# S107D.net
KiCad netlist of a schematic drawn in EAGLE
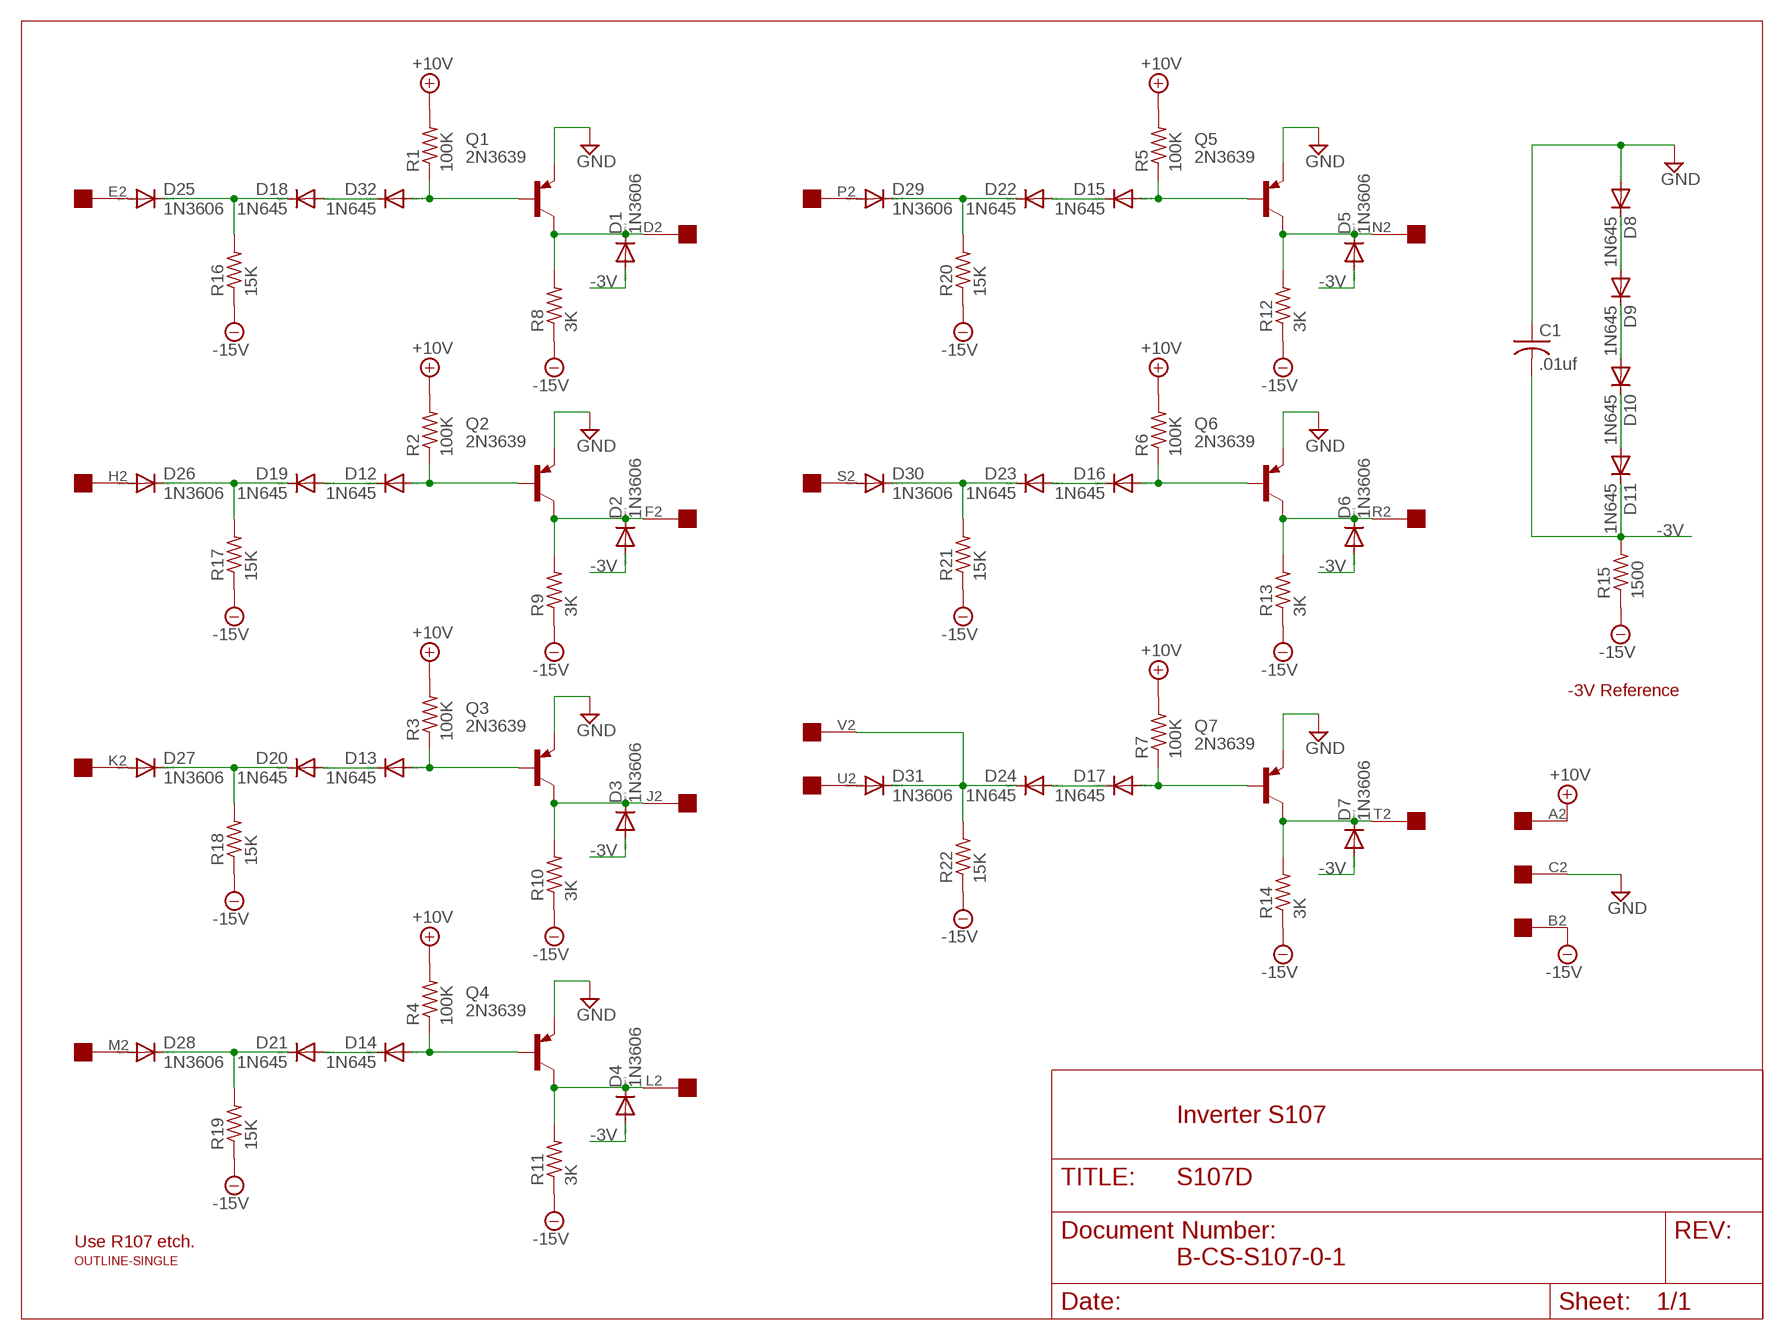
[diagram p0: schematic, sheet 1]

(export (version "E")
  (design (tool "Eeschema 10.0.6"))
  (components
    (comp (ref "C1")
      (value ".01uf")
      (footprint "eagle-import:C050-025X075")
      (libsource (lib "eagle-import") (part "C-US050-025X075"))
    )
    (comp (ref "D1")
      (value "1N3606")
      (footprint "eagle-import:DO35-10")
      (libsource (lib "eagle-import") (part "1N4148DO35-10"))
    )
    (comp (ref "D2")
      (value "1N3606")
      (footprint "eagle-import:DO35-10")
      (libsource (lib "eagle-import") (part "1N4148DO35-10"))
    )
    (comp (ref "D3")
      (value "1N3606")
      (footprint "eagle-import:DO35-10")
      (libsource (lib "eagle-import") (part "1N4148DO35-10"))
    )
    (comp (ref "D4")
      (value "1N3606")
      (footprint "eagle-import:DO35-10")
      (libsource (lib "eagle-import") (part "1N4148DO35-10"))
    )
    (comp (ref "D5")
      (value "1N3606")
      (footprint "eagle-import:DO35-10")
      (libsource (lib "eagle-import") (part "1N4148DO35-10"))
    )
    (comp (ref "D6")
      (value "1N3606")
      (footprint "eagle-import:DO35-10")
      (libsource (lib "eagle-import") (part "1N4148DO35-10"))
    )
    (comp (ref "D7")
      (value "1N3606")
      (footprint "eagle-import:DO35-10")
      (libsource (lib "eagle-import") (part "1N4148DO35-10"))
    )
    (comp (ref "D8")
      (value "1N645")
      (footprint "eagle-import:DO35-10")
      (libsource (lib "eagle-import") (part "1N4148DO35-10"))
    )
    (comp (ref "D9")
      (value "1N645")
      (footprint "eagle-import:DO35-10")
      (libsource (lib "eagle-import") (part "1N4148DO35-10"))
    )
    (comp (ref "D10")
      (value "1N645")
      (footprint "eagle-import:DO35-10")
      (libsource (lib "eagle-import") (part "1N4148DO35-10"))
    )
    (comp (ref "D11")
      (value "1N645")
      (footprint "eagle-import:DO35-10")
      (libsource (lib "eagle-import") (part "1N4148DO35-10"))
    )
    (comp (ref "D12")
      (value "1N645")
      (footprint "eagle-import:DO35-10")
      (libsource (lib "eagle-import") (part "1N4148DO35-10"))
    )
    (comp (ref "D13")
      (value "1N645")
      (footprint "eagle-import:DO35-10")
      (libsource (lib "eagle-import") (part "1N4148DO35-10"))
    )
    (comp (ref "D14")
      (value "1N645")
      (footprint "eagle-import:DO35-10")
      (libsource (lib "eagle-import") (part "1N4148DO35-10"))
    )
    (comp (ref "D15")
      (value "1N645")
      (footprint "eagle-import:DO35-10")
      (libsource (lib "eagle-import") (part "1N4148DO35-10"))
    )
    (comp (ref "D16")
      (value "1N645")
      (footprint "eagle-import:DO35-10")
      (libsource (lib "eagle-import") (part "1N4148DO35-10"))
    )
    (comp (ref "D17")
      (value "1N645")
      (footprint "eagle-import:DO35-10")
      (libsource (lib "eagle-import") (part "1N4148DO35-10"))
    )
    (comp (ref "D18")
      (value "1N645")
      (footprint "eagle-import:DO35-10")
      (libsource (lib "eagle-import") (part "1N4148DO35-10"))
    )
    (comp (ref "D19")
      (value "1N645")
      (footprint "eagle-import:DO35-10")
      (libsource (lib "eagle-import") (part "1N4148DO35-10"))
    )
    (comp (ref "D20")
      (value "1N645")
      (footprint "eagle-import:DO35-10")
      (libsource (lib "eagle-import") (part "1N4148DO35-10"))
    )
    (comp (ref "D21")
      (value "1N645")
      (footprint "eagle-import:DO35-10")
      (libsource (lib "eagle-import") (part "1N4148DO35-10"))
    )
    (comp (ref "D22")
      (value "1N645")
      (footprint "eagle-import:DO35-10")
      (libsource (lib "eagle-import") (part "1N4148DO35-10"))
    )
    (comp (ref "D23")
      (value "1N645")
      (footprint "eagle-import:DO35-10")
      (libsource (lib "eagle-import") (part "1N4148DO35-10"))
    )
    (comp (ref "D24")
      (value "1N645")
      (footprint "eagle-import:DO35-10")
      (libsource (lib "eagle-import") (part "1N4148DO35-10"))
    )
    (comp (ref "D25")
      (value "1N3606")
      (footprint "eagle-import:DO35-10")
      (libsource (lib "eagle-import") (part "1N4148DO35-10"))
    )
    (comp (ref "D26")
      (value "1N3606")
      (footprint "eagle-import:DO35-10")
      (libsource (lib "eagle-import") (part "1N4148DO35-10"))
    )
    (comp (ref "D27")
      (value "1N3606")
      (footprint "eagle-import:DO35-10")
      (libsource (lib "eagle-import") (part "1N4148DO35-10"))
    )
    (comp (ref "D28")
      (value "1N3606")
      (footprint "eagle-import:DO35-10")
      (libsource (lib "eagle-import") (part "1N4148DO35-10"))
    )
    (comp (ref "D29")
      (value "1N3606")
      (footprint "eagle-import:DO35-10")
      (libsource (lib "eagle-import") (part "1N4148DO35-10"))
    )
    (comp (ref "D30")
      (value "1N3606")
      (footprint "eagle-import:DO35-10")
      (libsource (lib "eagle-import") (part "1N4148DO35-10"))
    )
    (comp (ref "D31")
      (value "1N3606")
      (footprint "eagle-import:DO35-10")
      (libsource (lib "eagle-import") (part "1N4148DO35-10"))
    )
    (comp (ref "D32")
      (value "1N645")
      (footprint "eagle-import:DO35-10")
      (libsource (lib "eagle-import") (part "1N4148DO35-10"))
    )
    (comp (ref "Q1")
      (value "2N3639")
      (footprint "eagle-import:TO39")
      (libsource (lib "eagle-import") (part "2N3637"))
    )
    (comp (ref "Q2")
      (value "2N3639")
      (footprint "eagle-import:TO39")
      (libsource (lib "eagle-import") (part "2N3637"))
    )
    (comp (ref "Q3")
      (value "2N3639")
      (footprint "eagle-import:TO39")
      (libsource (lib "eagle-import") (part "2N3637"))
    )
    (comp (ref "Q4")
      (value "2N3639")
      (footprint "eagle-import:TO39")
      (libsource (lib "eagle-import") (part "2N3637"))
    )
    (comp (ref "Q5")
      (value "2N3639")
      (footprint "eagle-import:TO39")
      (libsource (lib "eagle-import") (part "2N3637"))
    )
    (comp (ref "Q6")
      (value "2N3639")
      (footprint "eagle-import:TO39")
      (libsource (lib "eagle-import") (part "2N3637"))
    )
    (comp (ref "Q7")
      (value "2N3639")
      (footprint "eagle-import:TO39")
      (libsource (lib "eagle-import") (part "2N3637"))
    )
    (comp (ref "R1")
      (value "100K")
      (footprint "eagle-import:0207_10")
      (libsource (lib "eagle-import") (part "R-US_0207/10"))
    )
    (comp (ref "R2")
      (value "100K")
      (footprint "eagle-import:0207_10")
      (libsource (lib "eagle-import") (part "R-US_0207/10"))
    )
    (comp (ref "R3")
      (value "100K")
      (footprint "eagle-import:0207_10")
      (libsource (lib "eagle-import") (part "R-US_0207/10"))
    )
    (comp (ref "R4")
      (value "100K")
      (footprint "eagle-import:0207_10")
      (libsource (lib "eagle-import") (part "R-US_0207/10"))
    )
    (comp (ref "R5")
      (value "100K")
      (footprint "eagle-import:0207_10")
      (libsource (lib "eagle-import") (part "R-US_0207/10"))
    )
    (comp (ref "R6")
      (value "100K")
      (footprint "eagle-import:0207_10")
      (libsource (lib "eagle-import") (part "R-US_0207/10"))
    )
    (comp (ref "R7")
      (value "100K")
      (footprint "eagle-import:0207_10")
      (libsource (lib "eagle-import") (part "R-US_0207/10"))
    )
    (comp (ref "R8")
      (value "3K")
      (footprint "eagle-import:0207_10")
      (libsource (lib "eagle-import") (part "R-US_0207/10"))
    )
    (comp (ref "R9")
      (value "3K")
      (footprint "eagle-import:0207_10")
      (libsource (lib "eagle-import") (part "R-US_0207/10"))
    )
    (comp (ref "R10")
      (value "3K")
      (footprint "eagle-import:0207_10")
      (libsource (lib "eagle-import") (part "R-US_0207/10"))
    )
    (comp (ref "R11")
      (value "3K")
      (footprint "eagle-import:0207_10")
      (libsource (lib "eagle-import") (part "R-US_0207/10"))
    )
    (comp (ref "R12")
      (value "3K")
      (footprint "eagle-import:0207_10")
      (libsource (lib "eagle-import") (part "R-US_0207/10"))
    )
    (comp (ref "R13")
      (value "3K")
      (footprint "eagle-import:0207_10")
      (libsource (lib "eagle-import") (part "R-US_0207/10"))
    )
    (comp (ref "R14")
      (value "3K")
      (footprint "eagle-import:0207_10")
      (libsource (lib "eagle-import") (part "R-US_0207/10"))
    )
    (comp (ref "R15")
      (value "1500")
      (footprint "eagle-import:0207_10")
      (libsource (lib "eagle-import") (part "R-US_0207/10"))
    )
    (comp (ref "R16")
      (value "15K")
      (footprint "eagle-import:0207_10")
      (libsource (lib "eagle-import") (part "R-US_0207/10"))
    )
    (comp (ref "R17")
      (value "15K")
      (footprint "eagle-import:0207_10")
      (libsource (lib "eagle-import") (part "R-US_0207/10"))
    )
    (comp (ref "R18")
      (value "15K")
      (footprint "eagle-import:0207_10")
      (libsource (lib "eagle-import") (part "R-US_0207/10"))
    )
    (comp (ref "R19")
      (value "15K")
      (footprint "eagle-import:0207_10")
      (libsource (lib "eagle-import") (part "R-US_0207/10"))
    )
    (comp (ref "R20")
      (value "15K")
      (footprint "eagle-import:0207_10")
      (libsource (lib "eagle-import") (part "R-US_0207/10"))
    )
    (comp (ref "R21")
      (value "15K")
      (footprint "eagle-import:0207_10")
      (libsource (lib "eagle-import") (part "R-US_0207/10"))
    )
    (comp (ref "R22")
      (value "15K")
      (footprint "eagle-import:0207_10")
      (libsource (lib "eagle-import") (part "R-US_0207/10"))
    )
    (comp (ref "U$1")
      (value "OUTLINE-SINGLE")
      (footprint "eagle-import:SINGLE")
      (libsource (lib "eagle-import") (part "OUTLINE-SINGLE"))
    )
    (comp (ref "U$2")
      (value "EDGE-1")
      (footprint "eagle-import:EDGE-CON1")
      (libsource (lib "eagle-import") (part "EDGE-1"))
    )
  )
  (nets
    (net (code "1") (name "+10V") (class "Default")
      (node (ref "R1") (pin "2") (pinfunction "2_2") (pintype "passive"))
      (node (ref "R2") (pin "2") (pinfunction "2_2") (pintype "passive"))
      (node (ref "R3") (pin "2") (pinfunction "2_2") (pintype "passive"))
      (node (ref "R4") (pin "2") (pinfunction "2_2") (pintype "passive"))
      (node (ref "R5") (pin "2") (pinfunction "2_2") (pintype "passive"))
      (node (ref "R6") (pin "2") (pinfunction "2_2") (pintype "passive"))
      (node (ref "R7") (pin "2") (pinfunction "2_2") (pintype "passive"))
      (node (ref "U$2") (pin "A2") (pinfunction "1_A2") (pintype "bidirectional"))
    )
    (net (code "2") (name "-15V") (class "Default")
      (node (ref "R10") (pin "1") (pinfunction "1_1") (pintype "passive"))
      (node (ref "R11") (pin "1") (pinfunction "1_1") (pintype "passive"))
      (node (ref "R12") (pin "1") (pinfunction "1_1") (pintype "passive"))
      (node (ref "R13") (pin "1") (pinfunction "1_1") (pintype "passive"))
      (node (ref "R14") (pin "1") (pinfunction "1_1") (pintype "passive"))
      (node (ref "R15") (pin "1") (pinfunction "1_1") (pintype "passive"))
      (node (ref "R16") (pin "1") (pinfunction "1_1") (pintype "passive"))
      (node (ref "R17") (pin "1") (pinfunction "1_1") (pintype "passive"))
      (node (ref "R18") (pin "1") (pinfunction "1_1") (pintype "passive"))
      (node (ref "R19") (pin "1") (pinfunction "1_1") (pintype "passive"))
      (node (ref "R20") (pin "1") (pinfunction "1_1") (pintype "passive"))
      (node (ref "R21") (pin "1") (pinfunction "1_1") (pintype "passive"))
      (node (ref "R22") (pin "1") (pinfunction "1_1") (pintype "passive"))
      (node (ref "R8") (pin "1") (pinfunction "1_1") (pintype "passive"))
      (node (ref "R9") (pin "1") (pinfunction "1_1") (pintype "passive"))
      (node (ref "U$2") (pin "B2") (pinfunction "1_B2") (pintype "bidirectional"))
    )
    (net (code "3") (name "/-3V") (class "Default")
      (node (ref "C1") (pin "2") (pinfunction "2_2") (pintype "passive"))
      (node (ref "D1") (pin "A") (pinfunction "A_A") (pintype "passive"))
      (node (ref "D11") (pin "C") (pinfunction "C_C") (pintype "passive"))
      (node (ref "D2") (pin "A") (pinfunction "A_A") (pintype "passive"))
      (node (ref "D3") (pin "A") (pinfunction "A_A") (pintype "passive"))
      (node (ref "D4") (pin "A") (pinfunction "A_A") (pintype "passive"))
      (node (ref "D5") (pin "A") (pinfunction "A_A") (pintype "passive"))
      (node (ref "D6") (pin "A") (pinfunction "A_A") (pintype "passive"))
      (node (ref "D7") (pin "A") (pinfunction "A_A") (pintype "passive"))
      (node (ref "R15") (pin "2") (pinfunction "2_2") (pintype "passive"))
    )
    (net (code "4") (name "GND") (class "Default")
      (node (ref "C1") (pin "1") (pinfunction "1_1") (pintype "passive"))
      (node (ref "D8") (pin "A") (pinfunction "A_A") (pintype "passive"))
      (node (ref "Q1") (pin "1") (pinfunction "E_1") (pintype "passive"))
      (node (ref "Q2") (pin "1") (pinfunction "E_1") (pintype "passive"))
      (node (ref "Q3") (pin "1") (pinfunction "E_1") (pintype "passive"))
      (node (ref "Q4") (pin "1") (pinfunction "E_1") (pintype "passive"))
      (node (ref "Q5") (pin "1") (pinfunction "E_1") (pintype "passive"))
      (node (ref "Q6") (pin "1") (pinfunction "E_1") (pintype "passive"))
      (node (ref "Q7") (pin "1") (pinfunction "E_1") (pintype "passive"))
      (node (ref "U$2") (pin "C2") (pinfunction "1_C2") (pintype "bidirectional"))
    )
    (net (code "5") (name "Net-(D8-PadC)") (class "Default")
      (node (ref "D8") (pin "C") (pinfunction "C_C") (pintype "passive"))
      (node (ref "D9") (pin "A") (pinfunction "A_A") (pintype "passive"))
    )
    (net (code "6") (name "Net-(D10-PadA)") (class "Default")
      (node (ref "D10") (pin "A") (pinfunction "A_A") (pintype "passive"))
      (node (ref "D9") (pin "C") (pinfunction "C_C") (pintype "passive"))
    )
    (net (code "7") (name "Net-(D10-PadC)") (class "Default")
      (node (ref "D10") (pin "C") (pinfunction "C_C") (pintype "passive"))
      (node (ref "D11") (pin "A") (pinfunction "A_A") (pintype "passive"))
    )
    (net (code "8") (name "Net-(D12-PadC)") (class "Default")
      (node (ref "D12") (pin "C") (pinfunction "C_C") (pintype "passive"))
      (node (ref "D19") (pin "A") (pinfunction "A_A") (pintype "passive"))
    )
    (net (code "9") (name "Net-(D13-PadC)") (class "Default")
      (node (ref "D13") (pin "C") (pinfunction "C_C") (pintype "passive"))
      (node (ref "D20") (pin "A") (pinfunction "A_A") (pintype "passive"))
    )
    (net (code "10") (name "Net-(D14-PadC)") (class "Default")
      (node (ref "D14") (pin "C") (pinfunction "C_C") (pintype "passive"))
      (node (ref "D21") (pin "A") (pinfunction "A_A") (pintype "passive"))
    )
    (net (code "11") (name "Net-(D15-PadC)") (class "Default")
      (node (ref "D15") (pin "C") (pinfunction "C_C") (pintype "passive"))
      (node (ref "D22") (pin "A") (pinfunction "A_A") (pintype "passive"))
    )
    (net (code "12") (name "Net-(D16-PadC)") (class "Default")
      (node (ref "D16") (pin "C") (pinfunction "C_C") (pintype "passive"))
      (node (ref "D23") (pin "A") (pinfunction "A_A") (pintype "passive"))
    )
    (net (code "13") (name "Net-(D17-PadC)") (class "Default")
      (node (ref "D17") (pin "C") (pinfunction "C_C") (pintype "passive"))
      (node (ref "D24") (pin "A") (pinfunction "A_A") (pintype "passive"))
    )
    (net (code "14") (name "Net-(D18-PadA)") (class "Default")
      (node (ref "D18") (pin "A") (pinfunction "A_A") (pintype "passive"))
      (node (ref "D32") (pin "C") (pinfunction "C_C") (pintype "passive"))
    )
    (net (code "15") (name "Net-(D18-PadC)") (class "Default")
      (node (ref "D18") (pin "C") (pinfunction "C_C") (pintype "passive"))
      (node (ref "D25") (pin "C") (pinfunction "C_C") (pintype "passive"))
      (node (ref "R16") (pin "2") (pinfunction "2_2") (pintype "passive"))
    )
    (net (code "16") (name "Net-(D19-PadC)") (class "Default")
      (node (ref "D19") (pin "C") (pinfunction "C_C") (pintype "passive"))
      (node (ref "D26") (pin "C") (pinfunction "C_C") (pintype "passive"))
      (node (ref "R17") (pin "2") (pinfunction "2_2") (pintype "passive"))
    )
    (net (code "17") (name "Net-(D20-PadC)") (class "Default")
      (node (ref "D20") (pin "C") (pinfunction "C_C") (pintype "passive"))
      (node (ref "D27") (pin "C") (pinfunction "C_C") (pintype "passive"))
      (node (ref "R18") (pin "2") (pinfunction "2_2") (pintype "passive"))
    )
    (net (code "18") (name "Net-(D21-PadC)") (class "Default")
      (node (ref "D21") (pin "C") (pinfunction "C_C") (pintype "passive"))
      (node (ref "D28") (pin "C") (pinfunction "C_C") (pintype "passive"))
      (node (ref "R19") (pin "2") (pinfunction "2_2") (pintype "passive"))
    )
    (net (code "19") (name "Net-(D22-PadC)") (class "Default")
      (node (ref "D22") (pin "C") (pinfunction "C_C") (pintype "passive"))
      (node (ref "D29") (pin "C") (pinfunction "C_C") (pintype "passive"))
      (node (ref "R20") (pin "2") (pinfunction "2_2") (pintype "passive"))
    )
    (net (code "20") (name "Net-(D23-PadC)") (class "Default")
      (node (ref "D23") (pin "C") (pinfunction "C_C") (pintype "passive"))
      (node (ref "D30") (pin "C") (pinfunction "C_C") (pintype "passive"))
      (node (ref "R21") (pin "2") (pinfunction "2_2") (pintype "passive"))
    )
    (net (code "21") (name "Net-(Q1-B)") (class "Default")
      (node (ref "D32") (pin "A") (pinfunction "A_A") (pintype "passive"))
      (node (ref "Q1") (pin "2") (pinfunction "B_2") (pintype "passive"))
      (node (ref "R1") (pin "1") (pinfunction "1_1") (pintype "passive"))
    )
    (net (code "22") (name "Net-(Q1-C)") (class "Default")
      (node (ref "D1") (pin "C") (pinfunction "C_C") (pintype "passive"))
      (node (ref "Q1") (pin "3") (pinfunction "C_3") (pintype "passive"))
      (node (ref "R8") (pin "2") (pinfunction "2_2") (pintype "passive"))
      (node (ref "U$2") (pin "D2") (pinfunction "1_D2") (pintype "bidirectional"))
    )
    (net (code "23") (name "Net-(Q2-B)") (class "Default")
      (node (ref "D12") (pin "A") (pinfunction "A_A") (pintype "passive"))
      (node (ref "Q2") (pin "2") (pinfunction "B_2") (pintype "passive"))
      (node (ref "R2") (pin "1") (pinfunction "1_1") (pintype "passive"))
    )
    (net (code "24") (name "Net-(Q2-C)") (class "Default")
      (node (ref "D2") (pin "C") (pinfunction "C_C") (pintype "passive"))
      (node (ref "Q2") (pin "3") (pinfunction "C_3") (pintype "passive"))
      (node (ref "R9") (pin "2") (pinfunction "2_2") (pintype "passive"))
      (node (ref "U$2") (pin "F2") (pinfunction "1_F2") (pintype "bidirectional"))
    )
    (net (code "25") (name "Net-(Q3-B)") (class "Default")
      (node (ref "D13") (pin "A") (pinfunction "A_A") (pintype "passive"))
      (node (ref "Q3") (pin "2") (pinfunction "B_2") (pintype "passive"))
      (node (ref "R3") (pin "1") (pinfunction "1_1") (pintype "passive"))
    )
    (net (code "26") (name "Net-(Q3-C)") (class "Default")
      (node (ref "D3") (pin "C") (pinfunction "C_C") (pintype "passive"))
      (node (ref "Q3") (pin "3") (pinfunction "C_3") (pintype "passive"))
      (node (ref "R10") (pin "2") (pinfunction "2_2") (pintype "passive"))
      (node (ref "U$2") (pin "J2") (pinfunction "1_J2") (pintype "bidirectional"))
    )
    (net (code "27") (name "Net-(Q4-B)") (class "Default")
      (node (ref "D14") (pin "A") (pinfunction "A_A") (pintype "passive"))
      (node (ref "Q4") (pin "2") (pinfunction "B_2") (pintype "passive"))
      (node (ref "R4") (pin "1") (pinfunction "1_1") (pintype "passive"))
    )
    (net (code "28") (name "Net-(Q4-C)") (class "Default")
      (node (ref "D4") (pin "C") (pinfunction "C_C") (pintype "passive"))
      (node (ref "Q4") (pin "3") (pinfunction "C_3") (pintype "passive"))
      (node (ref "R11") (pin "2") (pinfunction "2_2") (pintype "passive"))
      (node (ref "U$2") (pin "L2") (pinfunction "1_L2") (pintype "bidirectional"))
    )
    (net (code "29") (name "Net-(Q5-B)") (class "Default")
      (node (ref "D15") (pin "A") (pinfunction "A_A") (pintype "passive"))
      (node (ref "Q5") (pin "2") (pinfunction "B_2") (pintype "passive"))
      (node (ref "R5") (pin "1") (pinfunction "1_1") (pintype "passive"))
    )
    (net (code "30") (name "Net-(Q5-C)") (class "Default")
      (node (ref "D5") (pin "C") (pinfunction "C_C") (pintype "passive"))
      (node (ref "Q5") (pin "3") (pinfunction "C_3") (pintype "passive"))
      (node (ref "R12") (pin "2") (pinfunction "2_2") (pintype "passive"))
      (node (ref "U$2") (pin "N2") (pinfunction "1_N2") (pintype "bidirectional"))
    )
    (net (code "31") (name "Net-(Q6-B)") (class "Default")
      (node (ref "D16") (pin "A") (pinfunction "A_A") (pintype "passive"))
      (node (ref "Q6") (pin "2") (pinfunction "B_2") (pintype "passive"))
      (node (ref "R6") (pin "1") (pinfunction "1_1") (pintype "passive"))
    )
    (net (code "32") (name "Net-(Q6-C)") (class "Default")
      (node (ref "D6") (pin "C") (pinfunction "C_C") (pintype "passive"))
      (node (ref "Q6") (pin "3") (pinfunction "C_3") (pintype "passive"))
      (node (ref "R13") (pin "2") (pinfunction "2_2") (pintype "passive"))
      (node (ref "U$2") (pin "R2") (pinfunction "1_R2") (pintype "bidirectional"))
    )
    (net (code "33") (name "Net-(Q7-B)") (class "Default")
      (node (ref "D17") (pin "A") (pinfunction "A_A") (pintype "passive"))
      (node (ref "Q7") (pin "2") (pinfunction "B_2") (pintype "passive"))
      (node (ref "R7") (pin "1") (pinfunction "1_1") (pintype "passive"))
    )
    (net (code "34") (name "Net-(Q7-C)") (class "Default")
      (node (ref "D7") (pin "C") (pinfunction "C_C") (pintype "passive"))
      (node (ref "Q7") (pin "3") (pinfunction "C_3") (pintype "passive"))
      (node (ref "R14") (pin "2") (pinfunction "2_2") (pintype "passive"))
      (node (ref "U$2") (pin "T2") (pinfunction "1_T2") (pintype "bidirectional"))
    )
    (net (code "35") (name "Net-(U$2E-1)") (class "Default")
      (node (ref "D25") (pin "A") (pinfunction "A_A") (pintype "passive"))
      (node (ref "U$2") (pin "E2") (pinfunction "1_E2") (pintype "bidirectional"))
    )
    (net (code "36") (name "Net-(U$2G-1)") (class "Default")
      (node (ref "D26") (pin "A") (pinfunction "A_A") (pintype "passive"))
      (node (ref "U$2") (pin "H2") (pinfunction "1_H2") (pintype "bidirectional"))
    )
    (net (code "37") (name "Net-(U$2I-1)") (class "Default")
      (node (ref "D27") (pin "A") (pinfunction "A_A") (pintype "passive"))
      (node (ref "U$2") (pin "K2") (pinfunction "1_K2") (pintype "bidirectional"))
    )
    (net (code "38") (name "Net-(U$2K-1)") (class "Default")
      (node (ref "D28") (pin "A") (pinfunction "A_A") (pintype "passive"))
      (node (ref "U$2") (pin "M2") (pinfunction "1_M2") (pintype "bidirectional"))
    )
    (net (code "39") (name "Net-(U$2M-1)") (class "Default")
      (node (ref "D29") (pin "A") (pinfunction "A_A") (pintype "passive"))
      (node (ref "U$2") (pin "P2") (pinfunction "1_P2") (pintype "bidirectional"))
    )
    (net (code "40") (name "Net-(U$2O-1)") (class "Default")
      (node (ref "D30") (pin "A") (pinfunction "A_A") (pintype "passive"))
      (node (ref "U$2") (pin "S2") (pinfunction "1_S2") (pintype "bidirectional"))
    )
    (net (code "41") (name "Net-(U$2Q-1)") (class "Default")
      (node (ref "D31") (pin "A") (pinfunction "A_A") (pintype "passive"))
      (node (ref "U$2") (pin "U2") (pinfunction "1_U2") (pintype "bidirectional"))
    )
    (net (code "42") (name "Net-(U$2R-1)") (class "Default")
      (node (ref "D24") (pin "C") (pinfunction "C_C") (pintype "passive"))
      (node (ref "D31") (pin "C") (pinfunction "C_C") (pintype "passive"))
      (node (ref "R22") (pin "2") (pinfunction "2_2") (pintype "passive"))
      (node (ref "U$2") (pin "V2") (pinfunction "1_V2") (pintype "bidirectional"))
    )
  )
)
